# Sheet3.net
KiCad netlist of a schematic drawn in Altium Designer
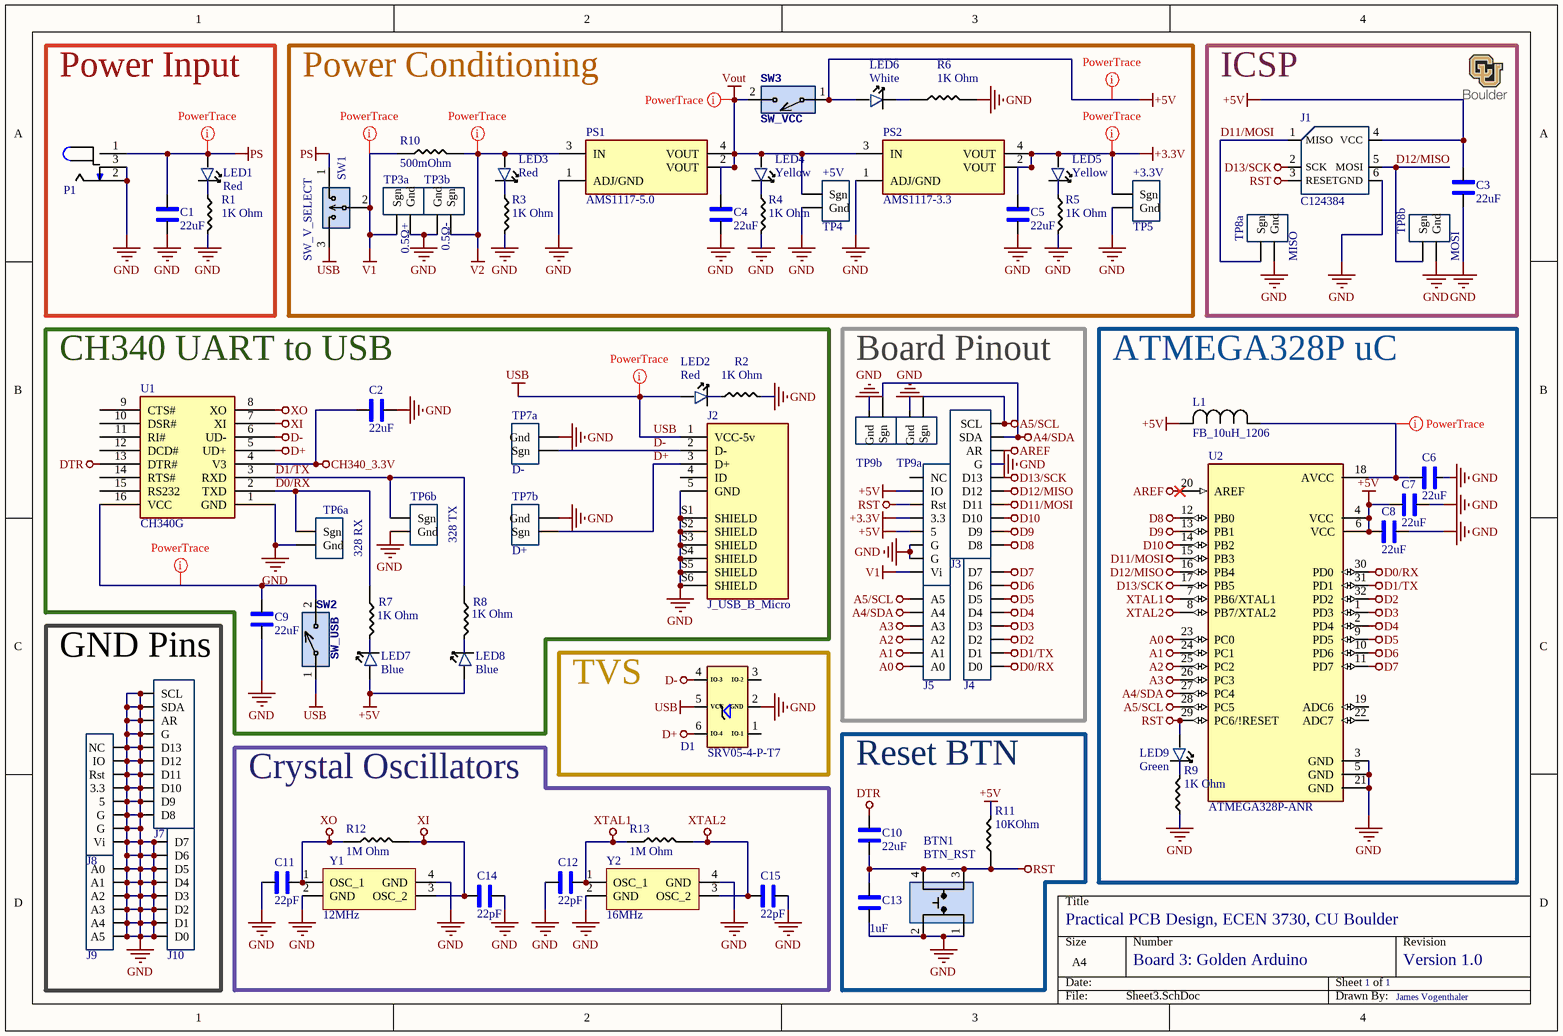
[diagram p0: Sheet3.SchDoc]

(export (version "E")
  (design (tool "Eeschema 10.0.6"))
  (components
    (comp (ref "BTN1")
      (value "BTN_RST")
      (footprint "Switch_JLC")
      (description "Tactile Switch SPST-NO Top Actuated Surface Mount")
      (fields (field (name "MFR PART #") "KH-4.5X4.5X4.3H-STM") (field (name "LCSC PART#") "C2837550"))
      (libsource (lib "ECEN5730Lib_2023_05_DS") (part "SW_Push_Button_JLC"))
    )
    (comp (ref "C1")
      (value "22uF")
      (footprint "1206_Passive_Capacitor")
      (description "22uF ±10% 25V X5R 1206 Multilayer Ceramic Capacitors MLCC - SMD/SMT RoHS")
      (fields (field (name "MFR PART #") "CL31A226KAHNNNE") (field (name "LCSC PART#") "C12891"))
      (libsource (lib "ECEN5730Lib_2023_05_DS") (part "C_22uF_1206"))
    )
    (comp (ref "C2")
      (value "22uF")
      (footprint "1206_Passive_Capacitor")
      (description "22uF ±10% 25V X5R 1206 Multilayer Ceramic Capacitors MLCC - SMD/SMT RoHS")
      (fields (field (name "MFR PART #") "CL31A226KAHNNNE") (field (name "LCSC PART#") "C12891"))
      (libsource (lib "ECEN5730Lib_2023_05_DS") (part "C_22uF_1206"))
    )
    (comp (ref "C3")
      (value "22uF")
      (footprint "1206_Passive_Capacitor")
      (description "22uF ±10% 25V X5R 1206 Multilayer Ceramic Capacitors MLCC - SMD/SMT RoHS")
      (fields (field (name "MFR PART #") "CL31A226KAHNNNE") (field (name "LCSC PART#") "C12891"))
      (libsource (lib "ECEN5730Lib_2023_05_DS") (part "C_22uF_1206"))
    )
    (comp (ref "C4")
      (value "22uF")
      (footprint "1206_Passive_Capacitor")
      (description "22uF ±10% 25V X5R 1206 Multilayer Ceramic Capacitors MLCC - SMD/SMT RoHS")
      (fields (field (name "MFR PART #") "CL31A226KAHNNNE") (field (name "LCSC PART#") "C12891"))
      (libsource (lib "ECEN5730Lib_2023_05_DS") (part "C_22uF_1206"))
    )
    (comp (ref "C5")
      (value "22uF")
      (footprint "1206_Passive_Capacitor")
      (description "22uF ±10% 25V X5R 1206 Multilayer Ceramic Capacitors MLCC - SMD/SMT RoHS")
      (fields (field (name "MFR PART #") "CL31A226KAHNNNE") (field (name "LCSC PART#") "C12891"))
      (libsource (lib "ECEN5730Lib_2023_05_DS") (part "C_22uF_1206"))
    )
    (comp (ref "C6")
      (value "22uF")
      (footprint "1206_Passive_Capacitor")
      (description "22uF ±10% 25V X5R 1206 Multilayer Ceramic Capacitors MLCC - SMD/SMT RoHS")
      (fields (field (name "MFR PART #") "CL31A226KAHNNNE") (field (name "LCSC PART#") "C12891"))
      (libsource (lib "ECEN5730Lib_2023_05_DS") (part "C_22uF_1206"))
    )
    (comp (ref "C7")
      (value "22uF")
      (footprint "1206_Passive_Capacitor")
      (description "22uF ±10% 25V X5R 1206 Multilayer Ceramic Capacitors MLCC - SMD/SMT RoHS")
      (fields (field (name "MFR PART #") "CL31A226KAHNNNE") (field (name "LCSC PART#") "C12891"))
      (libsource (lib "ECEN5730Lib_2023_05_DS") (part "C_22uF_1206"))
    )
    (comp (ref "C8")
      (value "22uF")
      (footprint "1206_Passive_Capacitor")
      (description "22uF ±10% 25V X5R 1206 Multilayer Ceramic Capacitors MLCC - SMD/SMT RoHS")
      (fields (field (name "MFR PART #") "CL31A226KAHNNNE") (field (name "LCSC PART#") "C12891"))
      (libsource (lib "ECEN5730Lib_2023_05_DS") (part "C_22uF_1206"))
    )
    (comp (ref "C9")
      (value "22uF")
      (footprint "1206_Passive_Capacitor")
      (description "22uF ±10% 25V X5R 1206 Multilayer Ceramic Capacitors MLCC - SMD/SMT RoHS")
      (fields (field (name "MFR PART #") "CL31A226KAHNNNE") (field (name "LCSC PART#") "C12891"))
      (libsource (lib "ECEN5730Lib_2023_05_DS") (part "C_22uF_1206"))
    )
    (comp (ref "C10")
      (value "22uF")
      (footprint "1206_Passive_Capacitor")
      (description "22uF ±10% 25V X5R 1206 Multilayer Ceramic Capacitors MLCC - SMD/SMT RoHS")
      (fields (field (name "MFR PART #") "CL31A226KAHNNNE") (field (name "LCSC PART#") "C12891"))
      (libsource (lib "ECEN5730Lib_2023_05_DS") (part "C_22uF_1206"))
    )
    (comp (ref "C11")
      (value "22pF")
      (footprint "1206_Passive_Capacitor")
      (description "22pF ±5% 1kV C0G 1206 Multilayer Ceramic Capacitors MLCC - SMD/SMT RoHS")
      (fields (field (name "LCSC PART#") "C107174") (field (name "MFR PART #") "CC1206JKNPOCBN220"))
      (libsource (lib "ECEN5730Lib_2023_05_DS") (part "C_22pF_1206"))
    )
    (comp (ref "C12")
      (value "22pF")
      (footprint "1206_Passive_Capacitor")
      (description "22pF ±5% 1kV C0G 1206 Multilayer Ceramic Capacitors MLCC - SMD/SMT RoHS")
      (fields (field (name "LCSC PART#") "C107174") (field (name "MFR PART #") "CC1206JKNPOCBN220"))
      (libsource (lib "ECEN5730Lib_2023_05_DS") (part "C_22pF_1206"))
    )
    (comp (ref "C13")
      (value "1uF")
      (footprint "1206_Passive_Capacitor")
      (description "MULTILAYER CERAMIC CAPACITORS MLCC - SMD/SMT 1UF 50V 1206 ROHS")
      (fields (field (name "MFR PART #") "CL31B105KBHNNNE") (field (name "LCSC PART#") "C1848"))
      (libsource (lib "ECEN5730Lib_2023_05_DS") (part "C_1uF_1206"))
    )
    (comp (ref "C14")
      (value "22pF")
      (footprint "1206_Passive_Capacitor")
      (description "22pF ±5% 1kV C0G 1206 Multilayer Ceramic Capacitors MLCC - SMD/SMT RoHS")
      (fields (field (name "LCSC PART#") "C107174") (field (name "MFR PART #") "CC1206JKNPOCBN220"))
      (libsource (lib "ECEN5730Lib_2023_05_DS") (part "C_22pF_1206"))
    )
    (comp (ref "C15")
      (value "22pF")
      (footprint "1206_Passive_Capacitor")
      (description "22pF ±5% 1kV C0G 1206 Multilayer Ceramic Capacitors MLCC - SMD/SMT RoHS")
      (fields (field (name "LCSC PART#") "C107174") (field (name "MFR PART #") "CC1206JKNPOCBN220"))
      (libsource (lib "ECEN5730Lib_2023_05_DS") (part "C_22pF_1206"))
    )
    (comp (ref "D1")
      (value "SRV05-4-P-T7")
      (footprint "TVS")
      (description "TVS SOT-23-6 ROHS")
      (fields (field (name "LCSC PART#") "C85364"))
      (libsource (lib "ECEN5730Lib_2023_05_DS") (part "D_TVS_Diode"))
    )
    (comp (ref "J1")
      (value "NRPN032PAEN-RC")
      (footprint "ICSP")
      (description "Connector Header Through Hole 6 position 0.079\" (2.00mm)")
      (fields (field (name "LCSC PART#") "C124384"))
      (libsource (lib "ECEN5730Lib_2023_05_DS") (part "J_ICSP"))
    )
    (comp (ref "J2")
      (value "J_USB_B_Micro")
      (footprint "AMPHENOL_10118194-0001LF")
      (description "Micro Usb, 2.0 Type b, Rcpt, Smt")
      (fields (field (name "MFR") "Amphenol ICC") (field (name "MFR PART #") "10118194-0001LF"))
      (libsource (lib "ECEN5730Lib_2023_05_DS") (part "J_USB_B_Micro"))
    )
    (comp (ref "J3")
      (value "PPTC101LFBN-RC")
      (footprint "10_PIN_ARDUINO_100MIL")
      (description "10 Position Header Connector 0.100\" (2.54mm) Through Hole Tin")
      (fields (field (name "LCSC PART#") "C225507"))
      (libsource (lib "ECEN5730Lib_2023_05_DS") (part "JF_10_PIN_FEMA_ARDUINO"))
    )
    (comp (ref "J4")
      (value "PPTC081LFBN-RC")
      (footprint "8_PIN_ARD-DIG_100MIL")
      (description "8 Position Header Connector 0.100\" (2.54mm) Through Hole Tin")
      (fields (field (name "LCSC PART#") "C27438"))
      (libsource (lib "ECEN5730Lib_2023_05_DS") (part "JF_8_PIN_FEMA_ARD-Dig"))
    )
    (comp (ref "J5")
      (value "PPTC061LFBN-RC")
      (footprint "6_PIN_ARD-Analog_100mil")
      (description "6 Position Header Connector 0.100\" (2.54mm) Through Hole Tin")
      (fields (field (name "LCSC PART#") "C40877"))
      (libsource (lib "") (part "JF_6_PIN_FEMA_ARD-Anolog_1"))
    )
    (comp (ref "J6")
      (value "PPTC081LFBN-RC")
      (footprint "8_PIN_ARD-PWR_100MIL")
      (description "8 Position Header Connector 0.100\" (2.54mm) Through Hole Tin")
      (fields (field (name "LCSC PART#") "C27438"))
      (libsource (lib "ECEN5730Lib_2023_05_DS") (part "JF_8_PIN_FEMA_ARD-Pwr"))
    )
    (comp (ref "J7")
      (value "PPTC101LFBN-RC")
      (footprint "10_PIN_ARDUINO_100MIL")
      (description "10 Position Header Connector 0.100\" (2.54mm) Through Hole Tin")
      (fields (field (name "LCSC PART#") "C225507"))
      (libsource (lib "") (part "JF_10_PIN_FEMA_ARDUINO_1"))
    )
    (comp (ref "J8")
      (value "PPTC081LFBN-RC")
      (footprint "8_PIN_ARD-PWR_100MIL")
      (description "8 Position Header Connector 0.100\" (2.54mm) Through Hole Tin")
      (fields (field (name "LCSC PART#") "C27438"))
      (libsource (lib "") (part "JF_8_PIN_FEMA_ARD-Pwr_1"))
    )
    (comp (ref "J9")
      (value "PPTC061LFBN-RC")
      (footprint "6_PIN_ARD-Analog_100mil")
      (description "6 Position Header Connector 0.100\" (2.54mm) Through Hole Tin")
      (fields (field (name "LCSC PART#") "C40877"))
      (libsource (lib "ECEN5730Lib_2023_05_DS") (part "JF_6_PIN_FEMA_ARD-Anolog"))
    )
    (comp (ref "J10")
      (value "PPTC081LFBN-RC")
      (footprint "8_PIN_ARD-DIG_100MIL")
      (description "8 Position Header Connector 0.100\" (2.54mm) Through Hole Tin")
      (fields (field (name "LCSC PART#") "C27438"))
      (libsource (lib "") (part "JF_8_PIN_FEMA_ARD-Dig_1"))
    )
    (comp (ref "L1")
      (value "FB_10uH_1206")
      (footprint "AIML-1206_ABR-M")
      (description "25mA 10uH ±10% 800mΩ 1206  Inductors (SMD) ROHS")
      (fields (field (name "MFR PART #") "CMI321609X100KT") (field (name "LCSC PART#") "C1051"))
      (libsource (lib "ECEN5730Lib_2023_05_DS") (part "FB_10uH_1206"))
    )
    (comp (ref "LED1")
      (value "Red")
      (footprint "LED_1206")
      (description "Red 621~631nm 1206 Light Emitting Diodes (LED) RoHS")
      (fields (field (name "MFR PART #") "15-21/R6C-FQ1R1B/2T") (field (name "LCSC PART#") "C93133"))
      (libsource (lib "ECEN5730Lib_2023_05_DS") (part "LED_RED_1206"))
    )
    (comp (ref "LED2")
      (value "Red")
      (footprint "LED_1206")
      (description "Red 621~631nm 1206 Light Emitting Diodes (LED) RoHS")
      (fields (field (name "MFR PART #") "15-21/R6C-FQ1R1B/2T") (field (name "LCSC PART#") "C93133"))
      (libsource (lib "ECEN5730Lib_2023_05_DS") (part "LED_RED_1206"))
    )
    (comp (ref "LED3")
      (value "Red")
      (footprint "LED_1206")
      (description "Red 621~631nm 1206 Light Emitting Diodes (LED) RoHS")
      (fields (field (name "MFR PART #") "15-21/R6C-FQ1R1B/2T") (field (name "LCSC PART#") "C93133"))
      (libsource (lib "ECEN5730Lib_2023_05_DS") (part "LED_RED_1206"))
    )
    (comp (ref "LED4")
      (value "Yellow")
      (footprint "LED_1206")
      (description "yellow 1206  Light Emitting Diodes (LED) ROHS")
      (fields (field (name "MFR PART #") "NCD1206Y1") (field (name "LCSC PART#") "C93094"))
      (libsource (lib "ECEN5730Lib_2023_05_DS") (part "LED_YELLOW_1206"))
    )
    (comp (ref "LED5")
      (value "Yellow")
      (footprint "LED_1206")
      (description "yellow 1206  Light Emitting Diodes (LED) ROHS")
      (fields (field (name "MFR PART #") "NCD1206Y1") (field (name "LCSC PART#") "C93094"))
      (libsource (lib "ECEN5730Lib_2023_05_DS") (part "LED_YELLOW_1206"))
    )
    (comp (ref "LED6")
      (value "White")
      (footprint "LED_1206")
      (description "White light 1206  Light Emitting Diodes (LED) ROHS")
      (fields (field (name "LCSC PART#") "C130718") (field (name "MFR PART #") "NCD1206W1"))
      (libsource (lib "ECEN5730Lib_2023_05_DS") (part "LED_WHITE_1206"))
    )
    (comp (ref "LED7")
      (value "Blue")
      (footprint "LED_1206")
      (description "blue 1206  Light Emitting Diodes (LED) ROHS")
      (fields (field (name "MFR PART #") "NCD1206B1") (field (name "LCSC PART#") "C130717"))
      (libsource (lib "ECEN5730Lib_2023_05_DS") (part "LED_BLUE_1206"))
    )
    (comp (ref "LED8")
      (value "Blue")
      (footprint "LED_1206")
      (description "blue 1206  Light Emitting Diodes (LED) ROHS")
      (fields (field (name "MFR PART #") "NCD1206B1") (field (name "LCSC PART#") "C130717"))
      (libsource (lib "ECEN5730Lib_2023_05_DS") (part "LED_BLUE_1206"))
    )
    (comp (ref "LED9")
      (value "Green")
      (footprint "LED_1206")
      (description "Green 513~528nm 1206 Light Emitting Diodes (LED) RoHS")
      (fields (field (name "MFR PART #") "SZYY1206G") (field (name "LCSC PART#") "C434439"))
      (libsource (lib "ECEN5730Lib_2023_05_DS") (part "LED_GREEN_1206"))
    )
    (comp (ref "P1")
      (value "Power Jack")
      (footprint "Power_Jack")
      (description "Power Barrel Connector Jack 2.10mm ID (0.083\"), 5.50mm OD (0.217\") Through Hole, Right Angle")
      (fields (field (name "MFR PART #") "PJ-102A") (field (name "LCSC PART#") "C136744"))
      (libsource (lib "ECEN5730Lib_2023_05_DS") (part "P_Power Jack"))
    )
    (comp (ref "PS1")
      (value "AMS1117-5.0")
      (footprint "LDO")
      (description "LOW DROPOUT REGULATORS(LDO) POSITIVE FIXED 1.3V @ 1A 15V 5V 1A SOT-223 ROHS")
      (fields (field (name "LCSC PART#") "C6187"))
      (libsource (lib "ECEN5730Lib_2023_05_DS") (part "PS_AMS_LDO_5V"))
    )
    (comp (ref "PS2")
      (value "AMS1117-3.3")
      (footprint "LDO")
      (description "LOW DROPOUT REGULATORS(LDO) POSITIVE FIXED 1.3V @ 800MA 15V 3.3V 1A SOT-223 ROHS")
      (fields (field (name "LCSC PART#") "C6186"))
      (libsource (lib "ECEN5730Lib_2023_05_DS") (part "PS_AMS_LDO_3v3"))
    )
    (comp (ref "R1")
      (value "1K Ohm")
      (footprint "1206_Passive_Resitor")
      (description "CHIP RESISTOR - SURFACE MOUNT 1KOHMS ±1% 1/4W 1206 ROHS")
      (fields (field (name "MFR PART #") "RNCP1206FTD1K00CT") (field (name "LCSC PART#") "C4410"))
      (libsource (lib "ECEN5730Lib_2023_05_DS") (part "R_1K_1206"))
    )
    (comp (ref "R2")
      (value "1K Ohm")
      (footprint "1206_Passive_Resitor")
      (description "CHIP RESISTOR - SURFACE MOUNT 1KOHMS ±1% 1/4W 1206 ROHS")
      (fields (field (name "MFR PART #") "RNCP1206FTD1K00CT") (field (name "LCSC PART#") "C4410"))
      (libsource (lib "ECEN5730Lib_2023_05_DS") (part "R_1K_1206"))
    )
    (comp (ref "R3")
      (value "1K Ohm")
      (footprint "1206_Passive_Resitor")
      (description "CHIP RESISTOR - SURFACE MOUNT 1KOHMS ±1% 1/4W 1206 ROHS")
      (fields (field (name "MFR PART #") "RNCP1206FTD1K00CT") (field (name "LCSC PART#") "C4410"))
      (libsource (lib "ECEN5730Lib_2023_05_DS") (part "R_1K_1206"))
    )
    (comp (ref "R4")
      (value "1K Ohm")
      (footprint "1206_Passive_Resitor")
      (description "CHIP RESISTOR - SURFACE MOUNT 1KOHMS ±1% 1/4W 1206 ROHS")
      (fields (field (name "MFR PART #") "RNCP1206FTD1K00CT") (field (name "LCSC PART#") "C4410"))
      (libsource (lib "ECEN5730Lib_2023_05_DS") (part "R_1K_1206"))
    )
    (comp (ref "R5")
      (value "1K Ohm")
      (footprint "1206_Passive_Resitor")
      (description "CHIP RESISTOR - SURFACE MOUNT 1KOHMS ±1% 1/4W 1206 ROHS")
      (fields (field (name "MFR PART #") "RNCP1206FTD1K00CT") (field (name "LCSC PART#") "C4410"))
      (libsource (lib "ECEN5730Lib_2023_05_DS") (part "R_1K_1206"))
    )
    (comp (ref "R6")
      (value "1K Ohm")
      (footprint "1206_Passive_Resitor")
      (description "CHIP RESISTOR - SURFACE MOUNT 1KOHMS ±1% 1/4W 1206 ROHS")
      (fields (field (name "MFR PART #") "RNCP1206FTD1K00CT") (field (name "LCSC PART#") "C4410"))
      (libsource (lib "ECEN5730Lib_2023_05_DS") (part "R_1K_1206"))
    )
    (comp (ref "R7")
      (value "1K Ohm")
      (footprint "1206_Passive_Resitor")
      (description "CHIP RESISTOR - SURFACE MOUNT 1KOHMS ±1% 1/4W 1206 ROHS")
      (fields (field (name "MFR PART #") "RNCP1206FTD1K00CT") (field (name "LCSC PART#") "C4410"))
      (libsource (lib "ECEN5730Lib_2023_05_DS") (part "R_1K_1206"))
    )
    (comp (ref "R8")
      (value "1K Ohm")
      (footprint "1206_Passive_Resitor")
      (description "CHIP RESISTOR - SURFACE MOUNT 1KOHMS ±1% 1/4W 1206 ROHS")
      (fields (field (name "MFR PART #") "RNCP1206FTD1K00CT") (field (name "LCSC PART#") "C4410"))
      (libsource (lib "ECEN5730Lib_2023_05_DS") (part "R_1K_1206"))
    )
    (comp (ref "R9")
      (value "1K Ohm")
      (footprint "1206_Passive_Resitor")
      (description "CHIP RESISTOR - SURFACE MOUNT 1KOHMS ±1% 1/4W 1206 ROHS")
      (fields (field (name "MFR PART #") "RNCP1206FTD1K00CT") (field (name "LCSC PART#") "C4410"))
      (libsource (lib "ECEN5730Lib_2023_05_DS") (part "R_1K_1206"))
    )
    (comp (ref "R10")
      (value "500mOhm")
      (footprint "1206_Passive_Resitor")
      (description "Resistors/Shunt 250mW 500mΩ ±800ppm/℃ ±5% 1206  Current Sense  Resistors ROHS")
      (fields (field (name "MFR PART #") "1206W4J050KT5E") (field (name "LCSC PART#") "C247433"))
      (libsource (lib "ECEN5730Lib_2023_05_DS") (part "R_500mOhm_1206"))
    )
    (comp (ref "R11")
      (value "10KOhm")
      (footprint "1206_Passive_Resitor")
      (description "10 kOhms ±5% 0.25W, 1/4W Chip Resistor 1206 (3216 Metric) Automotive AEC-Q200 Thick Film")
      (fields (field (name "MFR PART #") "RMCF1206FT10K0") (field (name "LCSC PART#") "C17902"))
      (libsource (lib "ECEN5730Lib_2023_05_DS") (part "R_10KOhm_1206"))
    )
    (comp (ref "R12")
      (value "1M Ohm")
      (footprint "1206_Passive_Resitor")
      (description "CHIP RESISTOR - SURFACE MOUNT 1MOHMS ±1% 1/4W 1206 ROHS")
      (fields (field (name "MFR PART #") "RMCF1206JT1M00") (field (name "LCSC PART#") "C17927"))
      (libsource (lib "ECEN5730Lib_2023_05_DS") (part "R_1M_1206"))
    )
    (comp (ref "R13")
      (value "1M Ohm")
      (footprint "1206_Passive_Resitor")
      (description "CHIP RESISTOR - SURFACE MOUNT 1MOHMS ±1% 1/4W 1206 ROHS")
      (fields (field (name "MFR PART #") "RMCF1206JT1M00") (field (name "LCSC PART#") "C17927"))
      (libsource (lib "ECEN5730Lib_2023_05_DS") (part "R_1M_1206"))
    )
    (comp (ref "SW1")
      (value "SW_V_SELECT")
      (footprint "3_PIN_100mil")
      (description "Connector Header Through Hole 3 position 0.100\" (2.54mm)")
      (fields (field (name "MFR PART #") "PREC003SAAN-RC") (field (name "LCSC PART#") "C49257"))
      (libsource (lib "ECEN5730Lib_2023_05_DS") (part "SW_3Pin_100mil_Switch"))
    )
    (comp (ref "SW2")
      (value "SW_USB")
      (footprint "2Pin-Header-Conn")
      (description "2Pin Header")
      (fields (field (name "LCSC PART#") "C124375"))
      (libsource (lib "ECEN5730Lib_2023_05_DS") (part "SW_2Pin_100mil_Switch"))
    )
    (comp (ref "SW3")
      (value "SW_VCC")
      (footprint "2Pin-Header-Conn")
      (description "2Pin Header")
      (fields (field (name "LCSC PART#") "C124375"))
      (libsource (lib "") (part "SW_2Pin_100mil_Switch_1"))
    )
    (comp (ref "TP3a")
      (value "0.5Ω+")
      (footprint "TP10x_Probe")
      (description "Test Point 300 mil centers")
      (libsource (lib "") (part "TP_10x_Probe_2"))
    )
    (comp (ref "TP3b")
      (value "0.5Ω-")
      (footprint "TP10x_Probe")
      (description "Test Point 300 mil centers")
      (libsource (lib "ECEN5730Lib_2023_05_DS") (part "TP_10x_Probe"))
    )
    (comp (ref "TP4")
      (value "+5V")
      (footprint "TP10x_Probe")
      (description "Test Point 300 mil centers")
      (libsource (lib "ECEN5730Lib_2023_05_DS") (part "TP_10x_Probe"))
    )
    (comp (ref "TP5")
      (value "+3.3V")
      (footprint "TP10x_Probe")
      (description "Test Point 300 mil centers")
      (libsource (lib "ECEN5730Lib_2023_05_DS") (part "TP_10x_Probe"))
    )
    (comp (ref "TP6a")
      (value "328 RX")
      (footprint "TP10x_Probe")
      (description "Test Point 300 mil centers")
      (libsource (lib "ECEN5730Lib_2023_05_DS") (part "TP_10x_Probe"))
    )
    (comp (ref "TP6b")
      (value "328 TX")
      (footprint "TP10x_Probe")
      (description "Test Point 300 mil centers")
      (libsource (lib "ECEN5730Lib_2023_05_DS") (part "TP_10x_Probe"))
    )
    (comp (ref "TP7a")
      (value "D-")
      (footprint "TP10x_Probe")
      (description "Test Point 300 mil centers")
      (libsource (lib "") (part "TP_10x_Probe_3"))
    )
    (comp (ref "TP7b")
      (value "D+")
      (footprint "TP10x_Probe")
      (description "Test Point 300 mil centers")
      (libsource (lib "") (part "TP_10x_Probe_3"))
    )
    (comp (ref "TP8a")
      (value "MISO")
      (footprint "TP10x_Probe")
      (description "Test Point 300 mil centers")
      (libsource (lib "") (part "TP_10x_Probe_2"))
    )
    (comp (ref "TP8b")
      (value "MOSI")
      (footprint "TP10x_Probe")
      (description "Test Point 300 mil centers")
      (libsource (lib "") (part "TP_10x_Probe_2"))
    )
    (comp (ref "TP9a")
      (value "SDA")
      (footprint "TP10x_Probe")
      (description "Test Point 300 mil centers")
      (libsource (lib "") (part "TP_10x_Probe_1"))
    )
    (comp (ref "TP9b")
      (value "SCL")
      (footprint "TP10x_Probe")
      (description "Test Point 300 mil centers")
      (libsource (lib "") (part "TP_10x_Probe_1"))
    )
    (comp (ref "U1")
      (value "CH340G")
      (footprint "USB to serial")
      (description "Transceiver USB 2.0 2Mbps SOP-16_150mil USB ICs RoHS")
      (fields (field (name "LCSC PART#") "C14267"))
      (libsource (lib "ECEN5730Lib_2023_05_DS") (part "U_USBtoSerial"))
    )
    (comp (ref "U2")
      (value "ATMEGA328P-ANR")
      (footprint "ATMega328P")
      (description "AVR AVR® ATmega Microcontroller IC 8-Bit 20MHz 32KB (16K x 16) FLASH 32-TQFP (7x7)")
      (fields (field (name "MFR PART #") "ATMEGA328P-AU") (field (name "LCSC PART#") "C14877"))
      (libsource (lib "ECEN5730Lib_2023_05_DS") (part "U_ATMega328P"))
    )
    (comp (ref "Y1")
      (value "12MHz")
      (footprint "Crystal resonator")
      (description "SMD Crystal Resonators 12MHz ±10ppm SMD-3225_4P RoHS")
      (fields (field (name "LCSC PART#") "C9002") (field (name "MFR PART #") "X322512MSB4SI"))
      (libsource (lib "ECEN5730Lib_2023_05_DS") (part "X_12MHz_Res"))
    )
    (comp (ref "Y2")
      (value "16MHz")
      (footprint "Crystal resonator")
      (description "±10ppm 16000000Hz -40℃~85℃ 贴片无源晶振 60Ω 9pF SMD3225-4P Crystals ROHS")
      (fields (field (name "LCSC PART#") "C13738") (field (name "MFR PART #") "X322516MLB4SI"))
      (libsource (lib "ECEN5730Lib_2023_05_DS") (part "X_16Mhz_Res"))
    )
  )
  (nets
    (net (code "1") (name "+3.3V") (class "Default")
      (node (ref "C5") (pin "2") (pinfunction "2_2") (pintype "passive"))
      (node (ref "J6") (pin "4") (pinfunction "3.3_4") (pintype "passive"))
      (node (ref "LED5") (pin "1") (pinfunction "1_1") (pintype "passive"))
      (node (ref "PS2") (pin "2") (pinfunction "VOUT_2") (pintype "power_in"))
      (node (ref "PS2") (pin "4") (pinfunction "VOUT_4") (pintype "power_in"))
      (node (ref "TP5") (pin "1") (pinfunction "Sgn_1") (pintype "passive"))
    )
    (net (code "2") (name "+5V") (class "Default")
      (node (ref "C3") (pin "2") (pinfunction "2_2") (pintype "passive"))
      (node (ref "C7") (pin "2") (pinfunction "2_2") (pintype "passive"))
      (node (ref "C8") (pin "2") (pinfunction "2_2") (pintype "passive"))
      (node (ref "J1") (pin "4") (pinfunction "VCC_4") (pintype "passive"))
      (node (ref "J6") (pin "2") (pinfunction "IO_2") (pintype "passive"))
      (node (ref "J6") (pin "5") (pinfunction "5_5") (pintype "passive"))
      (node (ref "L1") (pin "2") (pinfunction "2_2") (pintype "passive"))
      (node (ref "LED6") (pin "1") (pinfunction "1_1") (pintype "passive"))
      (node (ref "LED7") (pin "1") (pinfunction "1_1") (pintype "passive"))
      (node (ref "LED8") (pin "1") (pinfunction "1_1") (pintype "passive"))
      (node (ref "R11") (pin "2") (pinfunction "2_2") (pintype "passive"))
      (node (ref "SW3") (pin "1") (pinfunction "1_1") (pintype "passive"))
      (node (ref "U2") (pin "4") (pinfunction "VCC_4") (pintype "power_in"))
      (node (ref "U2") (pin "6") (pinfunction "VCC_6") (pintype "power_in"))
    )
    (net (code "3") (name "A0") (class "Default")
      (node (ref "J5") (pin "1") (pinfunction "A0_1") (pintype "passive"))
      (node (ref "U2") (pin "23") (pinfunction "PC0_23") (pintype "bidirectional"))
    )
    (net (code "4") (name "A1") (class "Default")
      (node (ref "J5") (pin "2") (pinfunction "A1_2") (pintype "passive"))
      (node (ref "U2") (pin "24") (pinfunction "PC1_24") (pintype "bidirectional"))
    )
    (net (code "5") (name "A2") (class "Default")
      (node (ref "J5") (pin "3") (pinfunction "A2_3") (pintype "passive"))
      (node (ref "U2") (pin "25") (pinfunction "PC2_25") (pintype "bidirectional"))
    )
    (net (code "6") (name "A3") (class "Default")
      (node (ref "J5") (pin "4") (pinfunction "A3_4") (pintype "passive"))
      (node (ref "U2") (pin "26") (pinfunction "PC3_26") (pintype "bidirectional"))
    )
    (net (code "7") (name "A4{slash}SDA") (class "Default")
      (node (ref "J3") (pin "2") (pinfunction "SDA_2") (pintype "passive"))
      (node (ref "J5") (pin "5") (pinfunction "A4_5") (pintype "passive"))
      (node (ref "TP9b") (pin "1") (pinfunction "Sgn_1") (pintype "passive"))
      (node (ref "U2") (pin "27") (pinfunction "PC4_27") (pintype "bidirectional"))
    )
    (net (code "8") (name "A5{slash}SCL") (class "Default")
      (node (ref "J3") (pin "1") (pinfunction "SCL_1") (pintype "passive"))
      (node (ref "J5") (pin "6") (pinfunction "A5_6") (pintype "passive"))
      (node (ref "TP9a") (pin "1") (pinfunction "Sgn_1") (pintype "passive"))
      (node (ref "U2") (pin "28") (pinfunction "PC5_28") (pintype "bidirectional"))
    )
    (net (code "9") (name "AREF") (class "Default")
      (node (ref "J3") (pin "3") (pinfunction "AR_3") (pintype "passive"))
      (node (ref "U2") (pin "20") (pinfunction "AREF_20") (pintype "input"))
    )
    (net (code "10") (name "CH340_3.3V") (class "Default")
      (node (ref "C2") (pin "2") (pinfunction "2_2") (pintype "passive"))
      (node (ref "U1") (pin "4") (pinfunction "V3_4") (pintype "passive"))
    )
    (net (code "11") (name "D+") (class "Default")
      (node (ref "D1") (pin "6") (pinfunction "IO-4_6") (pintype "passive"))
      (node (ref "J2") (pin "3") (pinfunction "D+_3") (pintype "passive"))
      (node (ref "TP7b") (pin "1") (pinfunction "Sgn_1") (pintype "passive"))
      (node (ref "U1") (pin "5") (pinfunction "UD+_5") (pintype "passive"))
    )
    (net (code "12") (name "D-") (class "Default")
      (node (ref "D1") (pin "4") (pinfunction "IO-3_4") (pintype "passive"))
      (node (ref "J2") (pin "2") (pinfunction "D-_2") (pintype "passive"))
      (node (ref "TP7a") (pin "1") (pinfunction "Sgn_1") (pintype "passive"))
      (node (ref "U1") (pin "6") (pinfunction "UD-_6") (pintype "passive"))
    )
    (net (code "13") (name "D0{slash}RX") (class "Default")
      (node (ref "J4") (pin "8") (pinfunction "D0_8") (pintype "passive"))
      (node (ref "R7") (pin "1") (pinfunction "1_1") (pintype "passive"))
      (node (ref "TP6a") (pin "1") (pinfunction "Sgn_1") (pintype "passive"))
      (node (ref "U1") (pin "2") (pinfunction "TXD_2") (pintype "passive"))
      (node (ref "U2") (pin "30") (pinfunction "PD0_30") (pintype "bidirectional"))
    )
    (net (code "14") (name "D1{slash}TX") (class "Default")
      (node (ref "J4") (pin "7") (pinfunction "D1_7") (pintype "passive"))
      (node (ref "R8") (pin "1") (pinfunction "1_1") (pintype "passive"))
      (node (ref "TP6b") (pin "1") (pinfunction "Sgn_1") (pintype "passive"))
      (node (ref "U1") (pin "3") (pinfunction "RXD_3") (pintype "passive"))
      (node (ref "U2") (pin "31") (pinfunction "PD1_31") (pintype "bidirectional"))
    )
    (net (code "15") (name "D2") (class "Default")
      (node (ref "J4") (pin "6") (pinfunction "D2_6") (pintype "passive"))
      (node (ref "U2") (pin "32") (pinfunction "PD2_32") (pintype "bidirectional"))
    )
    (net (code "16") (name "D3") (class "Default")
      (node (ref "J4") (pin "5") (pinfunction "D3_5") (pintype "passive"))
      (node (ref "U2") (pin "1") (pinfunction "PD3_1") (pintype "bidirectional"))
    )
    (net (code "17") (name "D4") (class "Default")
      (node (ref "J4") (pin "4") (pinfunction "D4_4") (pintype "passive"))
      (node (ref "U2") (pin "2") (pinfunction "PD4_2") (pintype "bidirectional"))
    )
    (net (code "18") (name "D5") (class "Default")
      (node (ref "J4") (pin "3") (pinfunction "D5_3") (pintype "passive"))
      (node (ref "U2") (pin "9") (pinfunction "PD5_9") (pintype "bidirectional"))
    )
    (net (code "19") (name "D6") (class "Default")
      (node (ref "J4") (pin "2") (pinfunction "D6_2") (pintype "passive"))
      (node (ref "U2") (pin "10") (pinfunction "PD6_10") (pintype "bidirectional"))
    )
    (net (code "20") (name "D7") (class "Default")
      (node (ref "J4") (pin "1") (pinfunction "D7_1") (pintype "passive"))
      (node (ref "U2") (pin "11") (pinfunction "PD7_11") (pintype "bidirectional"))
    )
    (net (code "21") (name "D8") (class "Default")
      (node (ref "J3") (pin "10") (pinfunction "D8_10") (pintype "passive"))
      (node (ref "U2") (pin "12") (pinfunction "PB0_12") (pintype "bidirectional"))
    )
    (net (code "22") (name "D9") (class "Default")
      (node (ref "J3") (pin "9") (pinfunction "D9_9") (pintype "passive"))
      (node (ref "U2") (pin "13") (pinfunction "PB1_13") (pintype "bidirectional"))
    )
    (net (code "23") (name "D10") (class "Default")
      (node (ref "J3") (pin "8") (pinfunction "D10_8") (pintype "passive"))
      (node (ref "U2") (pin "14") (pinfunction "PB2_14") (pintype "bidirectional"))
    )
    (net (code "24") (name "D11{slash}MOSI") (class "Default")
      (node (ref "J1") (pin "1") (pinfunction "MISO_1") (pintype "passive"))
      (node (ref "J3") (pin "7") (pinfunction "D11_7") (pintype "passive"))
      (node (ref "TP8a") (pin "1") (pinfunction "Sgn_1") (pintype "passive"))
      (node (ref "U2") (pin "15") (pinfunction "PB3_15") (pintype "bidirectional"))
    )
    (net (code "25") (name "D12{slash}MISO") (class "Default")
      (node (ref "J1") (pin "5") (pinfunction "MOSI_5") (pintype "passive"))
      (node (ref "J3") (pin "6") (pinfunction "D12_6") (pintype "passive"))
      (node (ref "TP8b") (pin "1") (pinfunction "Sgn_1") (pintype "passive"))
      (node (ref "U2") (pin "16") (pinfunction "PB4_16") (pintype "bidirectional"))
    )
    (net (code "26") (name "D13{slash}SCK") (class "Default")
      (node (ref "J1") (pin "2") (pinfunction "SCK_2") (pintype "passive"))
      (node (ref "J3") (pin "5") (pinfunction "D13_5") (pintype "passive"))
      (node (ref "U2") (pin "17") (pinfunction "PB5_17") (pintype "bidirectional"))
    )
    (net (code "27") (name "DTR") (class "Default")
      (node (ref "C10") (pin "1") (pinfunction "1_1") (pintype "passive"))
      (node (ref "U1") (pin "13") (pinfunction "DTR#_13") (pintype "passive"))
    )
    (net (code "28") (name "GND") (class "Default")
      (node (ref "BTN1") (pin "1") (pinfunction "1_1") (pintype "passive"))
      (node (ref "BTN1") (pin "2") (pinfunction "2_2") (pintype "passive"))
      (node (ref "C1") (pin "1") (pinfunction "1_1") (pintype "passive"))
      (node (ref "C11") (pin "2") (pinfunction "2_2") (pintype "passive"))
      (node (ref "C12") (pin "2") (pinfunction "2_2") (pintype "passive"))
      (node (ref "C13") (pin "1") (pinfunction "1_1") (pintype "passive"))
      (node (ref "C14") (pin "2") (pinfunction "2_2") (pintype "passive"))
      (node (ref "C15") (pin "2") (pinfunction "2_2") (pintype "passive"))
      (node (ref "C2") (pin "1") (pinfunction "1_1") (pintype "passive"))
      (node (ref "C3") (pin "1") (pinfunction "1_1") (pintype "passive"))
      (node (ref "C4") (pin "1") (pinfunction "1_1") (pintype "passive"))
      (node (ref "C5") (pin "1") (pinfunction "1_1") (pintype "passive"))
      (node (ref "C6") (pin "1") (pinfunction "1_1") (pintype "passive"))
      (node (ref "C7") (pin "1") (pinfunction "1_1") (pintype "passive"))
      (node (ref "C8") (pin "1") (pinfunction "1_1") (pintype "passive"))
      (node (ref "C9") (pin "1") (pinfunction "1_1") (pintype "passive"))
      (node (ref "D1") (pin "2") (pinfunction "GND_2") (pintype "passive"))
      (node (ref "J1") (pin "6") (pinfunction "GND_6") (pintype "passive"))
      (node (ref "J10") (pin "1") (pinfunction "D7_1") (pintype "passive"))
      (node (ref "J10") (pin "2") (pinfunction "D6_2") (pintype "passive"))
      (node (ref "J10") (pin "3") (pinfunction "D5_3") (pintype "passive"))
      (node (ref "J10") (pin "4") (pinfunction "D4_4") (pintype "passive"))
      (node (ref "J10") (pin "5") (pinfunction "D3_5") (pintype "passive"))
      (node (ref "J10") (pin "6") (pinfunction "D2_6") (pintype "passive"))
      (node (ref "J10") (pin "7") (pinfunction "D1_7") (pintype "passive"))
      (node (ref "J10") (pin "8") (pinfunction "D0_8") (pintype "passive"))
      (node (ref "J2") (pin "5") (pinfunction "GND_5") (pintype "passive"))
      (node (ref "J2") (pin "S1") (pinfunction "SHIELD_S1") (pintype "passive"))
      (node (ref "J2") (pin "S2") (pinfunction "SHIELD_S2") (pintype "passive"))
      (node (ref "J2") (pin "S3") (pinfunction "SHIELD_S3") (pintype "passive"))
      (node (ref "J2") (pin "S4") (pinfunction "SHIELD_S4") (pintype "passive"))
      (node (ref "J2") (pin "S5") (pinfunction "SHIELD_S5") (pintype "passive"))
      (node (ref "J2") (pin "S6") (pinfunction "SHIELD_S6") (pintype "passive"))
      (node (ref "J3") (pin "4") (pinfunction "G_4") (pintype "passive"))
      (node (ref "J6") (pin "6") (pinfunction "G_6") (pintype "passive"))
      (node (ref "J6") (pin "7") (pinfunction "G_7") (pintype "passive"))
      (node (ref "J7") (pin "1") (pinfunction "SCL_1") (pintype "passive"))
      (node (ref "J7") (pin "10") (pinfunction "D8_10") (pintype "passive"))
      (node (ref "J7") (pin "2") (pinfunction "SDA_2") (pintype "passive"))
      (node (ref "J7") (pin "3") (pinfunction "AR_3") (pintype "passive"))
      (node (ref "J7") (pin "4") (pinfunction "G_4") (pintype "passive"))
      (node (ref "J7") (pin "5") (pinfunction "D13_5") (pintype "passive"))
      (node (ref "J7") (pin "6") (pinfunction "D12_6") (pintype "passive"))
      (node (ref "J7") (pin "7") (pinfunction "D11_7") (pintype "passive"))
      (node (ref "J7") (pin "8") (pinfunction "D10_8") (pintype "passive"))
      (node (ref "J7") (pin "9") (pinfunction "D9_9") (pintype "passive"))
      (node (ref "J8") (pin "1") (pinfunction "NC_1") (pintype "passive"))
      (node (ref "J8") (pin "2") (pinfunction "IO_2") (pintype "passive"))
      (node (ref "J8") (pin "3") (pinfunction "Rst_3") (pintype "passive"))
      (node (ref "J8") (pin "4") (pinfunction "3.3_4") (pintype "passive"))
      (node (ref "J8") (pin "5") (pinfunction "5_5") (pintype "passive"))
      (node (ref "J8") (pin "6") (pinfunction "G_6") (pintype "passive"))
      (node (ref "J8") (pin "7") (pinfunction "G_7") (pintype "passive"))
      (node (ref "J8") (pin "8") (pinfunction "Vi_8") (pintype "passive"))
      (node (ref "J9") (pin "1") (pinfunction "A0_1") (pintype "passive"))
      (node (ref "J9") (pin "2") (pinfunction "A1_2") (pintype "passive"))
      (node (ref "J9") (pin "3") (pinfunction "A2_3") (pintype "passive"))
      (node (ref "J9") (pin "4") (pinfunction "A3_4") (pintype "passive"))
      (node (ref "J9") (pin "5") (pinfunction "A4_5") (pintype "passive"))
      (node (ref "J9") (pin "6") (pinfunction "A5_6") (pintype "passive"))
      (node (ref "P1") (pin "2") (pinfunction "2_2") (pintype "power_in"))
      (node (ref "P1") (pin "3") (pinfunction "3_3") (pintype "power_in"))
      (node (ref "PS1") (pin "1") (pinfunction "ADJ/GND_1") (pintype "passive"))
      (node (ref "PS2") (pin "1") (pinfunction "ADJ/GND_1") (pintype "passive"))
      (node (ref "R1") (pin "2") (pinfunction "2_2") (pintype "passive"))
      (node (ref "R2") (pin "2") (pinfunction "2_2") (pintype "passive"))
      (node (ref "R3") (pin "2") (pinfunction "2_2") (pintype "passive"))
      (node (ref "R4") (pin "2") (pinfunction "2_2") (pintype "passive"))
      (node (ref "R5") (pin "2") (pinfunction "2_2") (pintype "passive"))
      (node (ref "R6") (pin "2") (pinfunction "2_2") (pintype "passive"))
      (node (ref "R9") (pin "1") (pinfunction "1_1") (pintype "passive"))
      (node (ref "TP3a") (pin "2") (pinfunction "Gnd_2") (pintype "passive"))
      (node (ref "TP3b") (pin "2") (pinfunction "Gnd_2") (pintype "passive"))
      (node (ref "TP4") (pin "2") (pinfunction "Gnd_2") (pintype "passive"))
      (node (ref "TP5") (pin "2") (pinfunction "Gnd_2") (pintype "passive"))
      (node (ref "TP6a") (pin "2") (pinfunction "Gnd_2") (pintype "passive"))
      (node (ref "TP6b") (pin "2") (pinfunction "Gnd_2") (pintype "passive"))
      (node (ref "TP7a") (pin "2") (pinfunction "Gnd_2") (pintype "passive"))
      (node (ref "TP7b") (pin "2") (pinfunction "Gnd_2") (pintype "passive"))
      (node (ref "TP8a") (pin "2") (pinfunction "Gnd_2") (pintype "passive"))
      (node (ref "TP8b") (pin "2") (pinfunction "Gnd_2") (pintype "passive"))
      (node (ref "TP9a") (pin "2") (pinfunction "Gnd_2") (pintype "passive"))
      (node (ref "TP9b") (pin "2") (pinfunction "Gnd_2") (pintype "passive"))
      (node (ref "U1") (pin "1") (pinfunction "GND_1") (pintype "passive"))
      (node (ref "U2") (pin "21") (pinfunction "GND_21") (pintype "power_in"))
      (node (ref "U2") (pin "3") (pinfunction "GND_3") (pintype "power_in"))
      (node (ref "U2") (pin "5") (pinfunction "GND_5") (pintype "power_in"))
      (node (ref "Y1") (pin "2") (pinfunction "GND_2") (pintype "passive"))
      (node (ref "Y1") (pin "4") (pinfunction "GND_4") (pintype "passive"))
      (node (ref "Y2") (pin "2") (pinfunction "GND_2") (pintype "passive"))
      (node (ref "Y2") (pin "4") (pinfunction "GND_4") (pintype "passive"))
    )
    (net (code "29") (name "Net-(LED1-Pad2)") (class "Default")
      (node (ref "LED1") (pin "2") (pinfunction "2_2") (pintype "passive"))
      (node (ref "R1") (pin "1") (pinfunction "1_1") (pintype "passive"))
    )
    (net (code "30") (name "Net-(LED2-Pad2)") (class "Default")
      (node (ref "LED2") (pin "2") (pinfunction "2_2") (pintype "passive"))
      (node (ref "R2") (pin "1") (pinfunction "1_1") (pintype "passive"))
    )
    (net (code "31") (name "Net-(LED3-Pad2)") (class "Default")
      (node (ref "LED3") (pin "2") (pinfunction "2_2") (pintype "passive"))
      (node (ref "R3") (pin "1") (pinfunction "1_1") (pintype "passive"))
    )
    (net (code "32") (name "Net-(LED4-Pad2)") (class "Default")
      (node (ref "LED4") (pin "2") (pinfunction "2_2") (pintype "passive"))
      (node (ref "R4") (pin "1") (pinfunction "1_1") (pintype "passive"))
    )
    (net (code "33") (name "Net-(LED5-Pad2)") (class "Default")
      (node (ref "LED5") (pin "2") (pinfunction "2_2") (pintype "passive"))
      (node (ref "R5") (pin "1") (pinfunction "1_1") (pintype "passive"))
    )
    (net (code "34") (name "Net-(LED6-Pad2)") (class "Default")
      (node (ref "LED6") (pin "2") (pinfunction "2_2") (pintype "passive"))
      (node (ref "R6") (pin "1") (pinfunction "1_1") (pintype "passive"))
    )
    (net (code "35") (name "Net-(LED7-Pad2)") (class "Default")
      (node (ref "LED7") (pin "2") (pinfunction "2_2") (pintype "passive"))
      (node (ref "R7") (pin "2") (pinfunction "2_2") (pintype "passive"))
    )
    (net (code "36") (name "Net-(LED8-Pad2)") (class "Default")
      (node (ref "LED8") (pin "2") (pinfunction "2_2") (pintype "passive"))
      (node (ref "R8") (pin "2") (pinfunction "2_2") (pintype "passive"))
    )
    (net (code "37") (name "Net-(LED9-Pad2)") (class "Default")
      (node (ref "LED9") (pin "2") (pinfunction "2_2") (pintype "passive"))
      (node (ref "R9") (pin "2") (pinfunction "2_2") (pintype "passive"))
    )
    (net (code "38") (name "Net-(U1-VCC)") (class "Default")
      (node (ref "C9") (pin "2") (pinfunction "2_2") (pintype "passive"))
      (node (ref "SW2") (pin "2") (pinfunction "2_2") (pintype "passive"))
      (node (ref "U1") (pin "16") (pinfunction "VCC_16") (pintype "passive"))
    )
    (net (code "39") (name "Net-(U2-AVCC)") (class "Default")
      (node (ref "C6") (pin "2") (pinfunction "2_2") (pintype "passive"))
      (node (ref "L1") (pin "1") (pinfunction "1_1") (pintype "passive"))
      (node (ref "U2") (pin "18") (pinfunction "AVCC_18") (pintype "power_in"))
    )
    (net (code "40") (name "PS") (class "Default")
      (node (ref "C1") (pin "2") (pinfunction "2_2") (pintype "passive"))
      (node (ref "LED1") (pin "1") (pinfunction "1_1") (pintype "passive"))
      (node (ref "P1") (pin "1") (pinfunction "1_1") (pintype "power_in"))
      (node (ref "SW1") (pin "1") (pinfunction "1_1") (pintype "passive"))
    )
    (net (code "41") (name "RST") (class "Default")
      (node (ref "BTN1") (pin "3") (pinfunction "3_3") (pintype "passive"))
      (node (ref "BTN1") (pin "4") (pinfunction "4_4") (pintype "passive"))
      (node (ref "C10") (pin "2") (pinfunction "2_2") (pintype "passive"))
      (node (ref "C13") (pin "2") (pinfunction "2_2") (pintype "passive"))
      (node (ref "J1") (pin "3") (pinfunction "RESET_3") (pintype "passive"))
      (node (ref "J6") (pin "3") (pinfunction "Rst_3") (pintype "passive"))
      (node (ref "LED9") (pin "1") (pinfunction "1_1") (pintype "passive"))
      (node (ref "R11") (pin "1") (pinfunction "1_1") (pintype "passive"))
      (node (ref "U2") (pin "29") (pinfunction "PC6/!RESET_29") (pintype "bidirectional"))
    )
    (net (code "42") (name "USB") (class "Default")
      (node (ref "D1") (pin "5") (pinfunction "VCC_5") (pintype "passive"))
      (node (ref "J2") (pin "1") (pinfunction "VCC-5v_1") (pintype "power_in"))
      (node (ref "LED2") (pin "1") (pinfunction "1_1") (pintype "passive"))
      (node (ref "SW1") (pin "3") (pinfunction "3_3") (pintype "passive"))
      (node (ref "SW2") (pin "1") (pinfunction "1_1") (pintype "passive"))
    )
    (net (code "43") (name "V1") (class "Default")
      (node (ref "J6") (pin "8") (pinfunction "Vi_8") (pintype "passive"))
      (node (ref "R10") (pin "1") (pinfunction "1_1") (pintype "passive"))
      (node (ref "SW1") (pin "2") (pinfunction "2_2") (pintype "passive"))
      (node (ref "TP3a") (pin "1") (pinfunction "Sgn_1") (pintype "passive"))
    )
    (net (code "44") (name "V2") (class "Default")
      (node (ref "LED3") (pin "1") (pinfunction "1_1") (pintype "passive"))
      (node (ref "PS1") (pin "3") (pinfunction "IN_3") (pintype "power_in"))
      (node (ref "R10") (pin "2") (pinfunction "2_2") (pintype "passive"))
      (node (ref "TP3b") (pin "1") (pinfunction "Sgn_1") (pintype "passive"))
    )
    (net (code "45") (name "Vout") (class "Default")
      (node (ref "C4") (pin "2") (pinfunction "2_2") (pintype "passive"))
      (node (ref "LED4") (pin "1") (pinfunction "1_1") (pintype "passive"))
      (node (ref "PS1") (pin "2") (pinfunction "VOUT_2") (pintype "power_in"))
      (node (ref "PS1") (pin "4") (pinfunction "VOUT_4") (pintype "power_in"))
      (node (ref "PS2") (pin "3") (pinfunction "IN_3") (pintype "power_in"))
      (node (ref "SW3") (pin "2") (pinfunction "2_2") (pintype "passive"))
      (node (ref "TP4") (pin "1") (pinfunction "Sgn_1") (pintype "passive"))
    )
    (net (code "46") (name "XI") (class "Default")
      (node (ref "C14") (pin "1") (pinfunction "1_1") (pintype "passive"))
      (node (ref "R12") (pin "2") (pinfunction "2_2") (pintype "passive"))
      (node (ref "U1") (pin "7") (pinfunction "XI_7") (pintype "passive"))
      (node (ref "Y1") (pin "3") (pinfunction "OSC_2_3") (pintype "passive"))
    )
    (net (code "47") (name "XO") (class "Default")
      (node (ref "C11") (pin "1") (pinfunction "1_1") (pintype "passive"))
      (node (ref "R12") (pin "1") (pinfunction "1_1") (pintype "passive"))
      (node (ref "U1") (pin "8") (pinfunction "XO_8") (pintype "passive"))
      (node (ref "Y1") (pin "1") (pinfunction "OSC_1_1") (pintype "passive"))
    )
    (net (code "48") (name "XTAL1") (class "Default")
      (node (ref "C12") (pin "1") (pinfunction "1_1") (pintype "passive"))
      (node (ref "R13") (pin "1") (pinfunction "1_1") (pintype "passive"))
      (node (ref "U2") (pin "7") (pinfunction "PB6/XTAL1_7") (pintype "bidirectional"))
      (node (ref "Y2") (pin "1") (pinfunction "OSC_1_1") (pintype "passive"))
    )
    (net (code "49") (name "XTAL2") (class "Default")
      (node (ref "C15") (pin "1") (pinfunction "1_1") (pintype "passive"))
      (node (ref "R13") (pin "2") (pinfunction "2_2") (pintype "passive"))
      (node (ref "U2") (pin "8") (pinfunction "PB7/XTAL2_8") (pintype "bidirectional"))
      (node (ref "Y2") (pin "3") (pinfunction "OSC_2_3") (pintype "passive"))
    )
    (net (code "50") (name "unconnected-(D1-IO-1-Pad1)") (class "Default")
      (node (ref "D1") (pin "1") (pinfunction "IO-1_1") (pintype "passive"))
    )
    (net (code "51") (name "unconnected-(D1-IO-2-Pad3)") (class "Default")
      (node (ref "D1") (pin "3") (pinfunction "IO-2_3") (pintype "passive"))
    )
    (net (code "52") (name "unconnected-(J2-ID-Pad4)") (class "Default")
      (node (ref "J2") (pin "4") (pinfunction "ID_4") (pintype "passive"))
    )
    (net (code "53") (name "unconnected-(J6-NC-Pad1)") (class "Default")
      (node (ref "J6") (pin "1") (pinfunction "NC_1") (pintype "passive"))
    )
    (net (code "54") (name "unconnected-(U1-CTS#-Pad9)") (class "Default")
      (node (ref "U1") (pin "9") (pinfunction "CTS#_9") (pintype "passive"))
    )
    (net (code "55") (name "unconnected-(U1-DCD#-Pad12)") (class "Default")
      (node (ref "U1") (pin "12") (pinfunction "DCD#_12") (pintype "passive"))
    )
    (net (code "56") (name "unconnected-(U1-DSR#-Pad10)") (class "Default")
      (node (ref "U1") (pin "10") (pinfunction "DSR#_10") (pintype "passive"))
    )
    (net (code "57") (name "unconnected-(U1-RI#-Pad11)") (class "Default")
      (node (ref "U1") (pin "11") (pinfunction "RI#_11") (pintype "passive"))
    )
    (net (code "58") (name "unconnected-(U1-RS232-Pad15)") (class "Default")
      (node (ref "U1") (pin "15") (pinfunction "RS232_15") (pintype "passive"))
    )
    (net (code "59") (name "unconnected-(U1-RTS#-Pad14)") (class "Default")
      (node (ref "U1") (pin "14") (pinfunction "RTS#_14") (pintype "passive"))
    )
    (net (code "60") (name "unconnected-(U2-ADC6-Pad19)") (class "Default")
      (node (ref "U2") (pin "19") (pinfunction "ADC6_19") (pintype "bidirectional"))
    )
    (net (code "61") (name "unconnected-(U2-ADC7-Pad22)") (class "Default")
      (node (ref "U2") (pin "22") (pinfunction "ADC7_22") (pintype "bidirectional"))
    )
  )
)
